# ip_phone_c_codec.net
KiCad netlist of a schematic drawn in Altium Designer
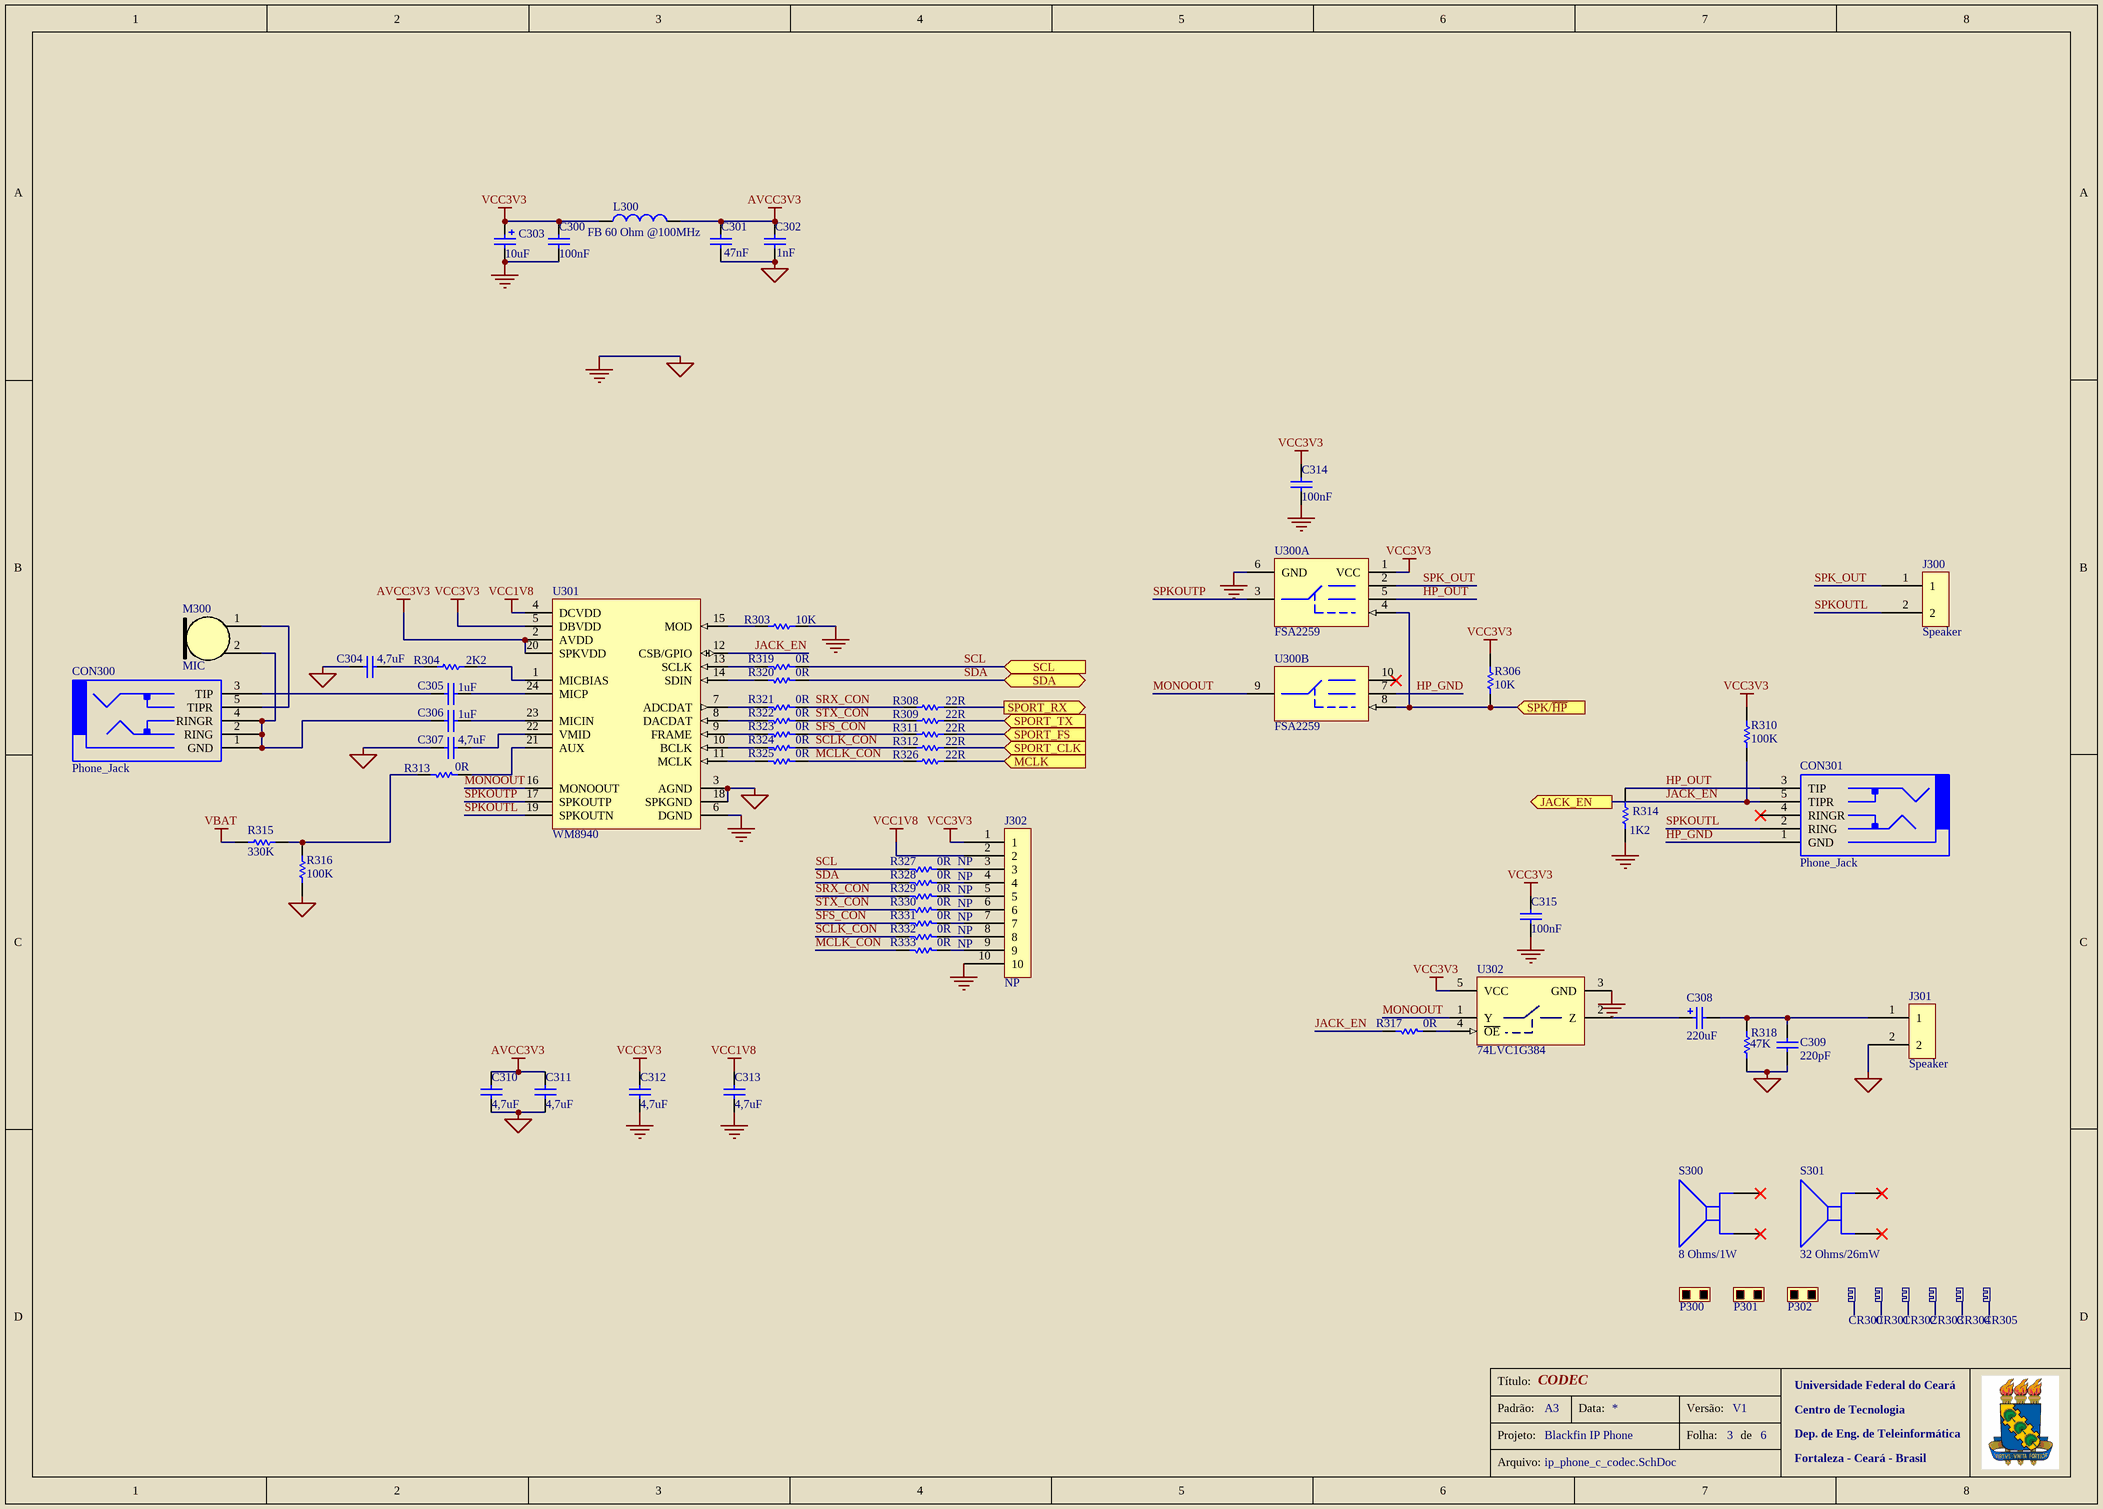
[diagram p0: ip_phone_c_codec.SchDoc]

(export (version "E")
  (design (tool "Eeschema 10.0.6"))
  (components
    (comp (ref "C300")
      (value "100nF")
      (footprint "ip_phone:CC1005-0402")
      (description "MLCC - SMD/SMT 100nF 16V 10% 0402")
      (fields (field (name "EVENDORPART#") "810-C1005X7R1C104K") (field (name "MANUFACTURER") "TDK"))
      (libsource (lib "ip_phone") (part "Capacitor"))
    )
    (comp (ref "C301")
      (value "47nF")
      (footprint "ip_phone:CC1005-0402")
      (description "MLCC - SMD/SMT 47nF 16V 10% 0402")
      (fields (field (name "EVENDORPART#") "311-1334-1-ND") (field (name "MANUFACTURER") "Yageo"))
      (libsource (lib "ip_phone") (part "Capacitor"))
    )
    (comp (ref "C302")
      (value "1nF")
      (footprint "ip_phone:CC1005-0402")
      (description "MLCC - SMD/SMT 1nF 16V 10% 0402")
      (fields (field (name "EVENDORPART#") "311-1352-1-ND") (field (name "MANUFACTURER") "Yageo"))
      (libsource (lib "ip_phone") (part "Capacitor"))
    )
    (comp (ref "C303")
      (value "10uF")
      (footprint "ip_phone:VE-100M0JTR-0305")
      (description "Aluminum Electrolytic Capacitors - SMD 6.3 Volts 10uF 20%")
      (fields (field (name "EVENDORPART#") "140-VE100M0JTR0305") (field (name "PART#") "VE-100M0JTR-0305"))
      (libsource (lib "ip_phone") (part "Capacitor_Electrolytic"))
    )
    (comp (ref "C304")
      (value "4,7uF")
      (footprint "ip_phone:CC1005-0402")
      (description "MLCC - SMD/SMT 4.7uF 20% 6.3Volts 0402")
      (fields (field (name "EVENDORPART#") "810-C1005X5R0J475M") (field (name "MANUFACTURER") "TDK"))
      (libsource (lib "ip_phone") (part "Capacitor"))
    )
    (comp (ref "C305")
      (value "1uF")
      (footprint "ip_phone:CC1005-0402")
      (description "CAP CER 1.0UF 6.3V 20% X5R 0402")
      (fields
        (field (name "EVENDORPART#") "490-1319-1-ND")
        (field (name "MANUFACTURER") "Murata Electronics North America")
      )
      (libsource (lib "ip_phone") (part "Capacitor"))
    )
    (comp (ref "C306")
      (value "1uF")
      (footprint "ip_phone:CC1005-0402")
      (description "CAP CER 1.0UF 6.3V 20% X5R 0402")
      (fields
        (field (name "EVENDORPART#") "490-1319-1-ND")
        (field (name "MANUFACTURER") "Murata Electronics North America")
      )
      (libsource (lib "ip_phone") (part "Capacitor"))
    )
    (comp (ref "C307")
      (value "4,7uF")
      (footprint "ip_phone:CC1005-0402")
      (description "MLCC - SMD/SMT 4.7uF 20% 6.3Volts 0402")
      (fields (field (name "EVENDORPART#") "810-C1005X5R0J475M") (field (name "MANUFACTURER") "TDK"))
      (libsource (lib "ip_phone") (part "Capacitor"))
    )
    (comp (ref "C308")
      (value "220uF")
      (footprint "ip_phone:CAP_VE221")
      (description "Aluminum Electrolytic Capacitors - SMD 6.3 Volts 220uF 20%")
      (fields (field (name "EVENDORPART#") "140-VE221M0JTR0605") (field (name "PART#") "VE-221M0JTR-0605"))
      (libsource (lib "ip_phone") (part "Capacitor_Electrolytic"))
    )
    (comp (ref "C309")
      (value "220pF")
      (footprint "ip_phone:CC1005-0402")
      (description "Capacitor 220pF 0402")
      (fields (field (name "EVENDORPART#") "311-1035-1-ND") (field (name "MANUFACTURER") "Yageo"))
      (libsource (lib "ip_phone") (part "Capacitor"))
    )
    (comp (ref "C310")
      (value "4,7uF")
      (footprint "ip_phone:CC1005-0402")
      (description "MLCC - SMD/SMT 4.7uF 20% 6.3Volts 0402")
      (fields (field (name "EVENDORPART#") "810-C1005X5R0J475M") (field (name "MANUFACTURER") "TDK"))
      (libsource (lib "ip_phone") (part "Capacitor"))
    )
    (comp (ref "C311")
      (value "4,7uF")
      (footprint "ip_phone:CC1005-0402")
      (description "MLCC - SMD/SMT 4.7uF 20% 6.3Volts 0402")
      (fields (field (name "EVENDORPART#") "810-C1005X5R0J475M") (field (name "MANUFACTURER") "TDK"))
      (libsource (lib "ip_phone") (part "Capacitor"))
    )
    (comp (ref "C312")
      (value "4,7uF")
      (footprint "ip_phone:CC1005-0402")
      (description "MLCC - SMD/SMT 4.7uF 20% 6.3Volts 0402")
      (fields (field (name "EVENDORPART#") "810-C1005X5R0J475M") (field (name "MANUFACTURER") "TDK"))
      (libsource (lib "ip_phone") (part "Capacitor"))
    )
    (comp (ref "C313")
      (value "4,7uF")
      (footprint "ip_phone:CC1005-0402")
      (description "MLCC - SMD/SMT 4.7uF 20% 6.3Volts 0402")
      (fields (field (name "EVENDORPART#") "810-C1005X5R0J475M") (field (name "MANUFACTURER") "TDK"))
      (libsource (lib "ip_phone") (part "Capacitor"))
    )
    (comp (ref "C314")
      (value "100nF")
      (footprint "ip_phone:CC1005-0402")
      (description "MLCC - SMD/SMT 0.1UF 16V 10% 0402")
      (fields (field (name "EVENDORPART#") "810-C1005X7R1C104K") (field (name "MANUFACTURER") "TDK"))
      (libsource (lib "ip_phone") (part "Capacitor"))
    )
    (comp (ref "C315")
      (value "100nF")
      (footprint "ip_phone:CC1005-0402")
      (description "MLCC - SMD/SMT 0.1UF 16V 10% 0402")
      (fields (field (name "EVENDORPART#") "810-C1005X7R1C104K") (field (name "MANUFACTURER") "TDK"))
      (libsource (lib "ip_phone") (part "Capacitor"))
    )
    (comp (ref "CON300")
      (value "Phone_Jack")
      (footprint "ip_phone:Phone_Jack")
      (fields
        (field (name "EVENDORPART#") "CP1-2535SJCT-ND")
        (field (name "MANUFACTURER") "CUI Inc")
        (field (name "PART#") "SJ1-2535-SMT")
      )
      (libsource (lib "") (part "Phone_Jack_1_1"))
    )
    (comp (ref "CON301")
      (value "Phone_Jack")
      (footprint "ip_phone:Phone_Jack")
      (fields
        (field (name "EVENDORPART#") "CP1-2535SJCT-ND")
        (field (name "MANUFACTURER") "CUI Inc")
        (field (name "PART#") "SJ1-2535-SMT")
      )
      (libsource (lib "ip_phone") (part "Phone_Jack_1"))
    )
    (comp (ref "CR300")
      (value "Crimp")
      (description "Socket Crimp")
      (fields (field (name "EVENDORPART#") "656-ILZC3A115000") (field (name "PART#") "IL-Z-C3-A-1-15000"))
      (libsource (lib "ip_phone") (part "Crimp"))
    )
    (comp (ref "CR301")
      (value "Crimp")
      (description "Socket Crimp")
      (fields (field (name "EVENDORPART#") "656-ILZC3A115000") (field (name "PART#") "IL-Z-C3-A-1-15000"))
      (libsource (lib "ip_phone") (part "Crimp"))
    )
    (comp (ref "CR302")
      (value "Crimp")
      (description "Socket Crimp")
      (fields (field (name "EVENDORPART#") "656-ILZC3A115000") (field (name "PART#") "IL-Z-C3-A-1-15000"))
      (libsource (lib "ip_phone") (part "Crimp"))
    )
    (comp (ref "CR303")
      (value "Crimp")
      (description "Socket Crimp")
      (fields (field (name "EVENDORPART#") "656-ILZC3A115000") (field (name "PART#") "IL-Z-C3-A-1-15000"))
      (libsource (lib "ip_phone") (part "Crimp"))
    )
    (comp (ref "CR304")
      (value "Crimp")
      (description "Socket Crimp")
      (fields (field (name "EVENDORPART#") "656-ILZC3A115000") (field (name "PART#") "IL-Z-C3-A-1-15000"))
      (libsource (lib "ip_phone") (part "Crimp"))
    )
    (comp (ref "CR305")
      (value "Crimp")
      (description "Socket Crimp")
      (fields (field (name "EVENDORPART#") "656-ILZC3A115000") (field (name "PART#") "IL-Z-C3-A-1-15000"))
      (libsource (lib "ip_phone") (part "Crimp"))
    )
    (comp (ref "J300")
      (value "Speaker")
      (footprint "ip_phone:CON_IL-Z-2PL")
      (description "Connector 2 Pin 1.25mm Male")
      (fields
        (field (name "EVENDORPART#") "656-IL-Z-2PL-SMTYE")
        (field (name "MANUFACTURER") "JAE Electronics")
      )
      (libsource (lib "ip_phone") (part "Speaker_con"))
    )
    (comp (ref "J301")
      (value "Speaker")
      (footprint "ip_phone:CON_IL-Z-2PL")
      (description "Connector 2 Pin 1.25mm Male")
      (fields
        (field (name "EVENDORPART#") "656-IL-Z-2PL-SMTYE")
        (field (name "MANUFACTURER") "JAE Electronics")
      )
      (libsource (lib "ip_phone") (part "Speaker_con"))
    )
    (comp (ref "J302")
      (value "CONN HEADER")
      (footprint "ip_phone:CONECTOR_10_PIN")
      (description "CONN HEADER .050\" 10POS PCB GOLD")
      (fields
        (field (name "EVENDORPART#") "S9014E-10-ND")
        (field (name "MANUFACTURER") "Sullins Connector Solutions")
        (field (name "NP") "NP")
      )
      (libsource (lib "ip_phone") (part "Conector 10pin"))
    )
    (comp (ref "L300")
      (value "FB 60 Ohm @100MHz")
      (footprint "ip_phone:INDUTOR_0603")
      (description "Ferrite Bead 60 Ohm @100MHz")
      (fields
        (field (name "EVENDORPART#") "667-EXC-3BP600H")
        (field (name "MANUFACTURER") "Panasonic Electronic Components")
      )
      (libsource (lib "ip_phone") (part "Inductor"))
    )
    (comp (ref "M300")
      (value "MIC")
      (footprint "ip_phone:CON_IL-Z-2PL")
      (description "Microphones -38DB 2VDC .5MA 2.2KOHM")
      (fields (field (name "PART#") "POM-2738P-C33-R") (field (name "MANUFACTURER") "PUI Audio"))
      (libsource (lib "ip_phone") (part "MIC"))
    )
    (comp (ref "P300")
      (value "Socket Housing")
      (description "Socket Housing 1.25mm 2 Pins")
      (fields (field (name "EVENDORPART#") "656-IL-Z-2S-S125C3") (field (name "PART#") "IL-Z-2S-S125C3"))
      (libsource (lib "ip_phone") (part "Socket Housing"))
    )
    (comp (ref "P301")
      (value "Socket Housing")
      (description "Socket Housing 1.25mm 2 Pins")
      (fields (field (name "EVENDORPART#") "656-IL-Z-2S-S125C3") (field (name "PART#") "IL-Z-2S-S125C3"))
      (libsource (lib "ip_phone") (part "Socket Housing"))
    )
    (comp (ref "P302")
      (value "Socket Housing")
      (description "Socket Housing 1.25mm 2 Pins")
      (fields (field (name "EVENDORPART#") "656-IL-Z-2S-S125C3") (field (name "PART#") "IL-Z-2S-S125C3"))
      (libsource (lib "ip_phone") (part "Socket Housing"))
    )
    (comp (ref "R303")
      (value "10K")
      (footprint "ip_phone:CR1005-0402")
      (description "Thick Film Resistors SMD 0402 10K 5%  1/16 W")
      (fields (field (name "EVENDORPART#") "311-10KJRCT-ND") (field (name "MANUFACTURER") "Yageo"))
      (libsource (lib "ip_phone") (part "Resistor"))
    )
    (comp (ref "R304")
      (value "2K2")
      (footprint "ip_phone:CR1005-0402")
      (description "Thick Film Resistors SMD 0402 2K2 5%  1/16 W")
      (fields (field (name "EVENDORPART#") "311-2.2KJRCT-ND") (field (name "MANUFACTURER") "Yageo"))
      (libsource (lib "ip_phone") (part "Resistor"))
    )
    (comp (ref "R306")
      (value "10K")
      (footprint "ip_phone:CR1005-0402")
      (description "Thick Film Resistors SMD 0402 10K 5%  1/16 W")
      (fields (field (name "EVENDORPART#") "311-10KJRCT-ND") (field (name "MANUFACTURER") "Yageo"))
      (libsource (lib "ip_phone") (part "Resistor"))
    )
    (comp (ref "R308")
      (value "22R")
      (footprint "ip_phone:CR1005-0402")
      (description "Thick Film Resistors SMD 0402 22R 5%  1/16 W")
      (fields (field (name "EVENDORPART#") "71-CRCW0402J-22-E3") (field (name "MANUFACTURER") "Vishay/Dale"))
      (libsource (lib "ip_phone") (part "Resistor"))
    )
    (comp (ref "R309")
      (value "22R")
      (footprint "ip_phone:CR1005-0402")
      (description "Thick Film Resistors SMD 0402 22R 5%  1/16 W")
      (fields (field (name "EVENDORPART#") "71-CRCW0402J-22-E3") (field (name "MANUFACTURER") "Vishay/Dale"))
      (libsource (lib "ip_phone") (part "Resistor"))
    )
    (comp (ref "R310")
      (value "100K")
      (footprint "ip_phone:CR1005-0402")
      (description "Thick Film Resistors SMD 0402 100K 5%  1/16 W")
      (fields (field (name "EVENDORPART#") "311-100KJRCT-ND") (field (name "MANUFACTURER") "Yageo"))
      (libsource (lib "ip_phone") (part "Resistor"))
    )
    (comp (ref "R311")
      (value "22R")
      (footprint "ip_phone:CR1005-0402")
      (description "Thick Film Resistors SMD 0402 22R 5%  1/16 W")
      (fields (field (name "EVENDORPART#") "71-CRCW0402J-22-E3") (field (name "MANUFACTURER") "Vishay/Dale"))
      (libsource (lib "ip_phone") (part "Resistor"))
    )
    (comp (ref "R312")
      (value "22R")
      (footprint "ip_phone:CR1005-0402")
      (description "Thick Film Resistors SMD 0402 22R 5%  1/16 W")
      (fields (field (name "EVENDORPART#") "71-CRCW0402J-22-E3") (field (name "MANUFACTURER") "Vishay/Dale"))
      (libsource (lib "ip_phone") (part "Resistor"))
    )
    (comp (ref "R313")
      (value "0R")
      (footprint "ip_phone:CR1005-0402")
      (description "Thick Film Resistors 0402 1/16W Jumper")
      (fields
        (field (name "EVENDORPART#") "667-ERJ-2GE0R00X")
        (field (name "MANUFACTURER") "Panasonic Electronic Components")
      )
      (libsource (lib "ip_phone") (part "Resistor"))
    )
    (comp (ref "R314")
      (value "1K2")
      (footprint "ip_phone:CR1005-0402")
      (description "Thick Film Resistors SMD 0402 1K2 5%  1/16 W")
      (fields (field (name "EVENDORPART#") "311-1.2KJRCT-ND") (field (name "MANUFACTURER") "Yageo"))
      (libsource (lib "ip_phone") (part "Resistor"))
    )
    (comp (ref "R315")
      (value "330K")
      (footprint "ip_phone:CR1005-0402")
      (description "Thick Film Resistor 330K 1% 1/16W")
      (fields
        (field (name "EVENDORPART#") "RMCF0402FT330KCT-ND")
        (field (name "MANUFACTURER") "Stackpole Electronics Inc")
      )
      (libsource (lib "ip_phone") (part "Resistor"))
    )
    (comp (ref "R316")
      (value "100K")
      (footprint "ip_phone:CR1005-0402")
      (description "Thick Film Resistors SMD 0402 100K 5%  1/16 W")
      (fields (field (name "EVENDORPART#") "311-100KJRCT-ND") (field (name "MANUFACTURER") "Yageo"))
      (libsource (lib "ip_phone") (part "Resistor"))
    )
    (comp (ref "R317")
      (value "0R")
      (footprint "ip_phone:CR1005-0402")
      (description "Thick Film Resistors 0402 1/16W Jumper")
      (fields
        (field (name "EVENDORPART#") "667-ERJ-2GE0R00X")
        (field (name "MANUFACTURER") "Panasonic Electronic Components")
      )
      (libsource (lib "ip_phone") (part "Resistor"))
    )
    (comp (ref "R318")
      (value "47K")
      (footprint "ip_phone:CR1005-0402")
      (description "Thick Film Resistors SMD 0402 47K 5%  1/16 W")
      (fields (field (name "EVENDORPART#") "311-47KJRCT-ND") (field (name "MANUFACTURER") "Yageo"))
      (libsource (lib "ip_phone") (part "Resistor"))
    )
    (comp (ref "R319")
      (value "0R")
      (footprint "ip_phone:CR1005-0402")
      (description "Thick Film Resistors 0402 1/16W Jumper")
      (fields
        (field (name "EVENDORPART#") "667-ERJ-2GE0R00X")
        (field (name "MANUFACTURER") "Panasonic Electronic Components")
      )
      (libsource (lib "ip_phone") (part "Resistor"))
    )
    (comp (ref "R320")
      (value "0R")
      (footprint "ip_phone:CR1005-0402")
      (description "Thick Film Resistors 0402 1/16W Jumper")
      (fields
        (field (name "EVENDORPART#") "667-ERJ-2GE0R00X")
        (field (name "MANUFACTURER") "Panasonic Electronic Components")
      )
      (libsource (lib "ip_phone") (part "Resistor"))
    )
    (comp (ref "R321")
      (value "0R")
      (footprint "ip_phone:CR1005-0402")
      (description "Thick Film Resistors 0402 1/16W Jumper")
      (fields
        (field (name "EVENDORPART#") "667-ERJ-2GE0R00X")
        (field (name "MANUFACTURER") "Panasonic Electronic Components")
      )
      (libsource (lib "ip_phone") (part "Resistor"))
    )
    (comp (ref "R322")
      (value "0R")
      (footprint "ip_phone:CR1005-0402")
      (description "Thick Film Resistors 0402 1/16W Jumper")
      (fields
        (field (name "EVENDORPART#") "667-ERJ-2GE0R00X")
        (field (name "MANUFACTURER") "Panasonic Electronic Components")
      )
      (libsource (lib "ip_phone") (part "Resistor"))
    )
    (comp (ref "R323")
      (value "0R")
      (footprint "ip_phone:CR1005-0402")
      (description "Thick Film Resistors 0402 1/16W Jumper")
      (fields
        (field (name "EVENDORPART#") "667-ERJ-2GE0R00X")
        (field (name "MANUFACTURER") "Panasonic Electronic Components")
      )
      (libsource (lib "ip_phone") (part "Resistor"))
    )
    (comp (ref "R324")
      (value "0R")
      (footprint "ip_phone:CR1005-0402")
      (description "Thick Film Resistors 0402 1/16W Jumper")
      (fields
        (field (name "EVENDORPART#") "667-ERJ-2GE0R00X")
        (field (name "MANUFACTURER") "Panasonic Electronic Components")
      )
      (libsource (lib "ip_phone") (part "Resistor"))
    )
    (comp (ref "R325")
      (value "0R")
      (footprint "ip_phone:CR1005-0402")
      (description "Thick Film Resistors 0402 1/16W Jumper")
      (fields
        (field (name "EVENDORPART#") "667-ERJ-2GE0R00X")
        (field (name "MANUFACTURER") "Panasonic Electronic Components")
      )
      (libsource (lib "ip_phone") (part "Resistor"))
    )
    (comp (ref "R326")
      (value "22R")
      (footprint "ip_phone:CR1005-0402")
      (description "Thick Film Resistors SMD 0402 22R 5%  1/16 W")
      (fields (field (name "EVENDORPART#") "71-CRCW0402J-22-E3") (field (name "MANUFACTURER") "Vishay/Dale"))
      (libsource (lib "ip_phone") (part "Resistor"))
    )
    (comp (ref "R327")
      (value "0R")
      (footprint "ip_phone:CR1005-0402")
      (description "Thick Film Resistors 0402 1/16W Jumper")
      (fields
        (field (name "EVENDORPART#") "667-ERJ-2GE0R00X")
        (field (name "MANUFACTURER") "Panasonic Electronic Components")
        (field (name "NP") "NP")
      )
      (libsource (lib "ip_phone") (part "Resistor"))
    )
    (comp (ref "R328")
      (value "0R")
      (footprint "ip_phone:CR1005-0402")
      (description "Thick Film Resistors 0402 1/16W Jumper")
      (fields
        (field (name "EVENDORPART#") "667-ERJ-2GE0R00X")
        (field (name "MANUFACTURER") "Panasonic Electronic Components")
        (field (name "NP") "NP")
      )
      (libsource (lib "ip_phone") (part "Resistor"))
    )
    (comp (ref "R329")
      (value "0R")
      (footprint "ip_phone:CR1005-0402")
      (description "Thick Film Resistors 0402 1/16W Jumper")
      (fields
        (field (name "EVENDORPART#") "667-ERJ-2GE0R00X")
        (field (name "MANUFACTURER") "Panasonic Electronic Components")
        (field (name "NP") "NP")
      )
      (libsource (lib "ip_phone") (part "Resistor"))
    )
    (comp (ref "R330")
      (value "0R")
      (footprint "ip_phone:CR1005-0402")
      (description "Thick Film Resistors 0402 1/16W Jumper")
      (fields
        (field (name "EVENDORPART#") "667-ERJ-2GE0R00X")
        (field (name "MANUFACTURER") "Panasonic Electronic Components")
        (field (name "NP") "NP")
      )
      (libsource (lib "ip_phone") (part "Resistor"))
    )
    (comp (ref "R331")
      (value "0R")
      (footprint "ip_phone:CR1005-0402")
      (description "Thick Film Resistors 0402 1/16W Jumper")
      (fields
        (field (name "EVENDORPART#") "667-ERJ-2GE0R00X")
        (field (name "MANUFACTURER") "Panasonic Electronic Components")
        (field (name "NP") "NP")
      )
      (libsource (lib "ip_phone") (part "Resistor"))
    )
    (comp (ref "R332")
      (value "0R")
      (footprint "ip_phone:CR1005-0402")
      (description "Thick Film Resistors 0402 1/16W Jumper")
      (fields
        (field (name "EVENDORPART#") "667-ERJ-2GE0R00X")
        (field (name "MANUFACTURER") "Panasonic Electronic Components")
        (field (name "NP") "NP")
      )
      (libsource (lib "ip_phone") (part "Resistor"))
    )
    (comp (ref "R333")
      (value "0R")
      (footprint "ip_phone:CR1005-0402")
      (description "Thick Film Resistors 0402 1/16W Jumper")
      (fields
        (field (name "EVENDORPART#") "667-ERJ-2GE0R00X")
        (field (name "MANUFACTURER") "Panasonic Electronic Components")
        (field (name "NP") "NP")
      )
      (libsource (lib "ip_phone") (part "Resistor"))
    )
    (comp (ref "S300")
      (value "8 Ohms/1W")
      (description "Speaker 8 Ohms 1W")
      (fields (field (name "EVENDORPART#") "254-DS238-RO") (field (name "MANUFACTURER") "Kobitone"))
      (libsource (lib "ip_phone") (part "Speaker"))
    )
    (comp (ref "S301")
      (value "32 Ohms/26mW")
      (description "Dynamic Receiver 32Ohms 26mW 115dB 13mm D")
      (fields (field (name "EVENDORPART#") "254-DR132-RO") (field (name "MANUFACTURER") "Kobitone"))
      (libsource (lib "ip_phone") (part "Receiver"))
    )
    (comp (ref "U300")
      (value "FSA2259")
      (footprint "ip_phone:QFN-10FSA")
      (description "Analog Switch, Dual SPDT")
      (fields
        (field (name "EVENDORPART#") "512-FSA2259UMX")
        (field (name "MANUFACTURER") "Fairchild Semiconductor")
      )
      (libsource (lib "ip_phone") (part "FSA2259"))
    )
    (comp (ref "U301")
      (value "WM8940")
      (footprint "ip_phone:QFN24")
      (description "Mono Audio CODEC")
      (fields (field (name "EVENDORPART#") "238-WM8940GEFL/V") (field (name "PART#") "WM8940GEFL/V"))
      (libsource (lib "ip_phone") (part "WM8940"))
    )
    (comp (ref "U302")
      (value "74LVC1G384")
      (footprint "ip_phone:SOT753")
      (description "Low Voltage SPST Analog Switch")
      (fields (field (name "EVENDORPART#") "771-LVC1G384GV125") (field (name "PART#") "74LVC1G384GV,125"))
      (libsource (lib "ip_phone") (part "74LVC1G384"))
    )
  )
  (nets
    (net (code "1") (name "/HP_GND") (class "Default")
      (node (ref "CON301") (pin "1") (pinfunction "GND_1") (pintype "passive"))
      (node (ref "U300") (pin "7") (pinfunction "2B0_7") (pintype "passive"))
    )
    (net (code "2") (name "/HP_OUT") (class "Default")
      (node (ref "CON301") (pin "3") (pinfunction "TIP_3") (pintype "passive"))
      (node (ref "R314") (pin "1") (pinfunction "1_1") (pintype "passive"))
      (node (ref "U300") (pin "5") (pinfunction "1B0_5") (pintype "passive"))
    )
    (net (code "3") (name "/JACK_EN") (class "Default")
      (node (ref "CON301") (pin "5") (pinfunction "TIPR_5") (pintype "passive"))
      (node (ref "R310") (pin "1") (pinfunction "1_1") (pintype "passive"))
      (node (ref "R317") (pin "2") (pinfunction "2_2") (pintype "passive"))
      (node (ref "U301") (pin "12") (pinfunction "CSB/GPIO_12") (pintype "bidirectional"))
    )
    (net (code "4") (name "/MCLK") (class "Default")
      (node (ref "R326") (pin "2") (pinfunction "2_2") (pintype "passive"))
    )
    (net (code "5") (name "/MCLK_CON") (class "Default")
      (node (ref "R325") (pin "1") (pinfunction "1_1") (pintype "passive"))
      (node (ref "R326") (pin "1") (pinfunction "1_1") (pintype "passive"))
      (node (ref "R333") (pin "2") (pinfunction "2_2") (pintype "passive"))
    )
    (net (code "6") (name "/MONOOUT") (class "Default")
      (node (ref "U300") (pin "9") (pinfunction "2A_9") (pintype "passive"))
      (node (ref "U301") (pin "16") (pinfunction "MONOOUT_16") (pintype "passive"))
      (node (ref "U302") (pin "1") (pinfunction "Y_1") (pintype "passive"))
    )
    (net (code "7") (name "/SCL") (class "Default")
      (node (ref "R319") (pin "1") (pinfunction "1_1") (pintype "passive"))
      (node (ref "R327") (pin "2") (pinfunction "2_2") (pintype "passive"))
    )
    (net (code "8") (name "/SCLK_CON") (class "Default")
      (node (ref "R312") (pin "1") (pinfunction "1_1") (pintype "passive"))
      (node (ref "R324") (pin "1") (pinfunction "1_1") (pintype "passive"))
      (node (ref "R332") (pin "2") (pinfunction "2_2") (pintype "passive"))
    )
    (net (code "9") (name "/SDA") (class "Default")
      (node (ref "R320") (pin "1") (pinfunction "1_1") (pintype "passive"))
      (node (ref "R328") (pin "2") (pinfunction "2_2") (pintype "passive"))
    )
    (net (code "10") (name "/SFS_CON") (class "Default")
      (node (ref "R311") (pin "1") (pinfunction "1_1") (pintype "passive"))
      (node (ref "R323") (pin "1") (pinfunction "1_1") (pintype "passive"))
      (node (ref "R331") (pin "2") (pinfunction "2_2") (pintype "passive"))
    )
    (net (code "11") (name "/SPKOUTL") (class "Default")
      (node (ref "CON301") (pin "2") (pinfunction "RING_2") (pintype "passive"))
      (node (ref "J300") (pin "2") (pinfunction "2_2") (pintype "passive"))
      (node (ref "U301") (pin "19") (pinfunction "SPKOUTN_19") (pintype "passive"))
    )
    (net (code "12") (name "/SPKOUTP") (class "Default")
      (node (ref "U300") (pin "3") (pinfunction "1A_3") (pintype "passive"))
      (node (ref "U301") (pin "17") (pinfunction "SPKOUTP_17") (pintype "passive"))
    )
    (net (code "13") (name "/SPK_OUT") (class "Default")
      (node (ref "J300") (pin "1") (pinfunction "1_1") (pintype "passive"))
      (node (ref "U300") (pin "2") (pinfunction "1B1_2") (pintype "passive"))
    )
    (net (code "14") (name "/SPK{slash}~{HP}") (class "Default")
      (node (ref "R306") (pin "1") (pinfunction "1_1") (pintype "passive"))
      (node (ref "U300") (pin "4") (pinfunction "S1_4") (pintype "input"))
      (node (ref "U300") (pin "8") (pinfunction "S2_8") (pintype "input"))
    )
    (net (code "15") (name "/SPORT_CLK") (class "Default")
      (node (ref "R312") (pin "2") (pinfunction "2_2") (pintype "passive"))
    )
    (net (code "16") (name "/SPORT_FS") (class "Default")
      (node (ref "R311") (pin "2") (pinfunction "2_2") (pintype "passive"))
    )
    (net (code "17") (name "/SPORT_RX") (class "Default")
      (node (ref "R308") (pin "2") (pinfunction "2_2") (pintype "passive"))
    )
    (net (code "18") (name "/SPORT_TX") (class "Default")
      (node (ref "R309") (pin "2") (pinfunction "2_2") (pintype "passive"))
    )
    (net (code "19") (name "/SRX_CON") (class "Default")
      (node (ref "R308") (pin "1") (pinfunction "1_1") (pintype "passive"))
      (node (ref "R321") (pin "1") (pinfunction "1_1") (pintype "passive"))
      (node (ref "R329") (pin "2") (pinfunction "2_2") (pintype "passive"))
    )
    (net (code "20") (name "/STX_CON") (class "Default")
      (node (ref "R309") (pin "1") (pinfunction "1_1") (pintype "passive"))
      (node (ref "R322") (pin "1") (pinfunction "1_1") (pintype "passive"))
      (node (ref "R330") (pin "2") (pinfunction "2_2") (pintype "passive"))
    )
    (net (code "21") (name "AGND") (class "Default")
      (node (ref "C300") (pin "1") (pinfunction "1_1") (pintype "passive"))
      (node (ref "C301") (pin "1") (pinfunction "1_1") (pintype "passive"))
      (node (ref "C302") (pin "1") (pinfunction "1_1") (pintype "passive"))
      (node (ref "C303") (pin "2") (pinfunction "2_2") (pintype "passive"))
      (node (ref "C304") (pin "1") (pinfunction "1_1") (pintype "passive"))
      (node (ref "C307") (pin "1") (pinfunction "1_1") (pintype "passive"))
      (node (ref "C309") (pin "1") (pinfunction "1_1") (pintype "passive"))
      (node (ref "C310") (pin "2") (pinfunction "2_2") (pintype "passive"))
      (node (ref "C311") (pin "2") (pinfunction "2_2") (pintype "passive"))
      (node (ref "C312") (pin "2") (pinfunction "2_2") (pintype "passive"))
      (node (ref "C313") (pin "2") (pinfunction "2_2") (pintype "passive"))
      (node (ref "C314") (pin "1") (pinfunction "1_1") (pintype "passive"))
      (node (ref "C315") (pin "1") (pinfunction "1_1") (pintype "passive"))
      (node (ref "J301") (pin "2") (pinfunction "2_2") (pintype "passive"))
      (node (ref "J302") (pin "10") (pinfunction "10_10") (pintype "passive"))
      (node (ref "R303") (pin "2") (pinfunction "2_2") (pintype "passive"))
      (node (ref "R314") (pin "2") (pinfunction "2_2") (pintype "passive"))
      (node (ref "R316") (pin "1") (pinfunction "1_1") (pintype "passive"))
      (node (ref "R318") (pin "2") (pinfunction "2_2") (pintype "passive"))
      (node (ref "U300") (pin "6") (pinfunction "GND_6") (pintype "power_in"))
      (node (ref "U301") (pin "18") (pinfunction "SPKGND_18") (pintype "passive"))
      (node (ref "U301") (pin "3") (pinfunction "AGND_3") (pintype "power_in"))
      (node (ref "U301") (pin "6") (pinfunction "DGND_6") (pintype "power_in"))
      (node (ref "U302") (pin "3") (pinfunction "GND_3") (pintype "power_in"))
    )
    (net (code "22") (name "AVCC3V3") (class "Default")
      (node (ref "C301") (pin "2") (pinfunction "2_2") (pintype "passive"))
      (node (ref "C302") (pin "2") (pinfunction "2_2") (pintype "passive"))
      (node (ref "C310") (pin "1") (pinfunction "1_1") (pintype "passive"))
      (node (ref "C311") (pin "1") (pinfunction "1_1") (pintype "passive"))
      (node (ref "L300") (pin "2") (pinfunction "2_2") (pintype "passive"))
      (node (ref "U301") (pin "2") (pinfunction "AVDD_2") (pintype "power_in"))
      (node (ref "U301") (pin "20") (pinfunction "SPKVDD_20") (pintype "power_in"))
    )
    (net (code "23") (name "Net-(C304-Pad2)") (class "Default")
      (node (ref "C304") (pin "2") (pinfunction "2_2") (pintype "passive"))
      (node (ref "R304") (pin "1") (pinfunction "1_1") (pintype "passive"))
    )
    (net (code "24") (name "Net-(C308-Pad2)") (class "Default")
      (node (ref "C308") (pin "2") (pinfunction "2_2") (pintype "passive"))
      (node (ref "C309") (pin "2") (pinfunction "2_2") (pintype "passive"))
      (node (ref "J301") (pin "1") (pinfunction "1_1") (pintype "passive"))
      (node (ref "R318") (pin "1") (pinfunction "1_1") (pintype "passive"))
    )
    (net (code "25") (name "Net-(CON300-GND)") (class "Default")
      (node (ref "C306") (pin "2") (pinfunction "2_2") (pintype "passive"))
      (node (ref "CON300") (pin "1") (pinfunction "GND_1") (pintype "passive"))
      (node (ref "CON300") (pin "2") (pinfunction "RING_2") (pintype "passive"))
      (node (ref "CON300") (pin "4") (pinfunction "RINGR_4") (pintype "passive"))
      (node (ref "M300") (pin "2") (pinfunction "GND_2") (pintype "power_in"))
    )
    (net (code "26") (name "Net-(CON300-TIP)") (class "Default")
      (node (ref "C305") (pin "2") (pinfunction "2_2") (pintype "passive"))
      (node (ref "CON300") (pin "3") (pinfunction "TIP_3") (pintype "passive"))
    )
    (net (code "27") (name "Net-(CON300-TIPR)") (class "Default")
      (node (ref "CON300") (pin "5") (pinfunction "TIPR_5") (pintype "passive"))
      (node (ref "M300") (pin "1") (pinfunction "OUT_1") (pintype "passive"))
    )
    (net (code "28") (name "Net-(J302-Pad3)") (class "Default")
      (node (ref "J302") (pin "3") (pinfunction "3_3") (pintype "passive"))
      (node (ref "R327") (pin "1") (pinfunction "1_1") (pintype "passive"))
    )
    (net (code "29") (name "Net-(J302-Pad4)") (class "Default")
      (node (ref "J302") (pin "4") (pinfunction "4_4") (pintype "passive"))
      (node (ref "R328") (pin "1") (pinfunction "1_1") (pintype "passive"))
    )
    (net (code "30") (name "Net-(J302-Pad5)") (class "Default")
      (node (ref "J302") (pin "5") (pinfunction "5_5") (pintype "passive"))
      (node (ref "R329") (pin "1") (pinfunction "1_1") (pintype "passive"))
    )
    (net (code "31") (name "Net-(J302-Pad6)") (class "Default")
      (node (ref "J302") (pin "6") (pinfunction "6_6") (pintype "passive"))
      (node (ref "R330") (pin "1") (pinfunction "1_1") (pintype "passive"))
    )
    (net (code "32") (name "Net-(J302-Pad7)") (class "Default")
      (node (ref "J302") (pin "7") (pinfunction "7_7") (pintype "passive"))
      (node (ref "R331") (pin "1") (pinfunction "1_1") (pintype "passive"))
    )
    (net (code "33") (name "Net-(J302-Pad8)") (class "Default")
      (node (ref "J302") (pin "8") (pinfunction "8_8") (pintype "passive"))
      (node (ref "R332") (pin "1") (pinfunction "1_1") (pintype "passive"))
    )
    (net (code "34") (name "Net-(J302-Pad9)") (class "Default")
      (node (ref "J302") (pin "9") (pinfunction "9_9") (pintype "passive"))
      (node (ref "R333") (pin "1") (pinfunction "1_1") (pintype "passive"))
    )
    (net (code "35") (name "Net-(R313-Pad2)") (class "Default")
      (node (ref "R313") (pin "2") (pinfunction "2_2") (pintype "passive"))
      (node (ref "R315") (pin "2") (pinfunction "2_2") (pintype "passive"))
      (node (ref "R316") (pin "2") (pinfunction "2_2") (pintype "passive"))
    )
    (net (code "36") (name "Net-(U301-ADCDAT)") (class "Default")
      (node (ref "R321") (pin "2") (pinfunction "2_2") (pintype "passive"))
      (node (ref "U301") (pin "7") (pinfunction "ADCDAT_7") (pintype "output"))
    )
    (net (code "37") (name "Net-(U301-AUX)") (class "Default")
      (node (ref "R313") (pin "1") (pinfunction "1_1") (pintype "passive"))
      (node (ref "U301") (pin "21") (pinfunction "AUX_21") (pintype "passive"))
    )
    (net (code "38") (name "Net-(U301-BCLK)") (class "Default")
      (node (ref "R324") (pin "2") (pinfunction "2_2") (pintype "passive"))
      (node (ref "U301") (pin "10") (pinfunction "BCLK_10") (pintype "input"))
    )
    (net (code "39") (name "Net-(U301-DACDAT)") (class "Default")
      (node (ref "R322") (pin "2") (pinfunction "2_2") (pintype "passive"))
      (node (ref "U301") (pin "8") (pinfunction "DACDAT_8") (pintype "input"))
    )
    (net (code "40") (name "Net-(U301-FRAME)") (class "Default")
      (node (ref "R323") (pin "2") (pinfunction "2_2") (pintype "passive"))
      (node (ref "U301") (pin "9") (pinfunction "FRAME_9") (pintype "input"))
    )
    (net (code "41") (name "Net-(U301-MCLK)") (class "Default")
      (node (ref "R325") (pin "2") (pinfunction "2_2") (pintype "passive"))
      (node (ref "U301") (pin "11") (pinfunction "MCLK_11") (pintype "input"))
    )
    (net (code "42") (name "Net-(U301-MICBIAS)") (class "Default")
      (node (ref "R304") (pin "2") (pinfunction "2_2") (pintype "passive"))
      (node (ref "U301") (pin "1") (pinfunction "MICBIAS_1") (pintype "passive"))
    )
    (net (code "43") (name "Net-(U301-MICIN)") (class "Default")
      (node (ref "C306") (pin "1") (pinfunction "1_1") (pintype "passive"))
      (node (ref "U301") (pin "23") (pinfunction "MICIN_23") (pintype "passive"))
    )
    (net (code "44") (name "Net-(U301-MICP)") (class "Default")
      (node (ref "C305") (pin "1") (pinfunction "1_1") (pintype "passive"))
      (node (ref "U301") (pin "24") (pinfunction "MICP_24") (pintype "passive"))
    )
    (net (code "45") (name "Net-(U301-MOD)") (class "Default")
      (node (ref "R303") (pin "1") (pinfunction "1_1") (pintype "passive"))
      (node (ref "U301") (pin "15") (pinfunction "MOD_15") (pintype "input"))
    )
    (net (code "46") (name "Net-(U301-SCLK)") (class "Default")
      (node (ref "R319") (pin "2") (pinfunction "2_2") (pintype "passive"))
      (node (ref "U301") (pin "13") (pinfunction "SCLK_13") (pintype "input"))
    )
    (net (code "47") (name "Net-(U301-SDIN)") (class "Default")
      (node (ref "R320") (pin "2") (pinfunction "2_2") (pintype "passive"))
      (node (ref "U301") (pin "14") (pinfunction "SDIN_14") (pintype "input"))
    )
    (net (code "48") (name "Net-(U301-VMID)") (class "Default")
      (node (ref "C307") (pin "2") (pinfunction "2_2") (pintype "passive"))
      (node (ref "U301") (pin "22") (pinfunction "VMID_22") (pintype "passive"))
    )
    (net (code "49") (name "Net-(U302-OE)") (class "Default")
      (node (ref "R317") (pin "1") (pinfunction "1_1") (pintype "passive"))
      (node (ref "U302") (pin "4") (pinfunction "OE_4") (pintype "input"))
    )
    (net (code "50") (name "Net-(U302-Z)") (class "Default")
      (node (ref "C308") (pin "1") (pinfunction "1_1") (pintype "passive"))
      (node (ref "U302") (pin "2") (pinfunction "Z_2") (pintype "passive"))
    )
    (net (code "51") (name "VBAT") (class "Default")
      (node (ref "R315") (pin "1") (pinfunction "1_1") (pintype "passive"))
    )
    (net (code "52") (name "VCC1V8") (class "Default")
      (node (ref "C313") (pin "1") (pinfunction "1_1") (pintype "passive"))
      (node (ref "J302") (pin "2") (pinfunction "2_2") (pintype "passive"))
      (node (ref "U301") (pin "4") (pinfunction "DCVDD_4") (pintype "power_in"))
    )
    (net (code "53") (name "VCC3V3") (class "Default")
      (node (ref "C300") (pin "2") (pinfunction "2_2") (pintype "passive"))
      (node (ref "C303") (pin "1") (pinfunction "1_1") (pintype "passive"))
      (node (ref "C312") (pin "1") (pinfunction "1_1") (pintype "passive"))
      (node (ref "C314") (pin "2") (pinfunction "2_2") (pintype "passive"))
      (node (ref "C315") (pin "2") (pinfunction "2_2") (pintype "passive"))
      (node (ref "J302") (pin "1") (pinfunction "1_1") (pintype "passive"))
      (node (ref "L300") (pin "1") (pinfunction "1_1") (pintype "passive"))
      (node (ref "R306") (pin "2") (pinfunction "2_2") (pintype "passive"))
      (node (ref "R310") (pin "2") (pinfunction "2_2") (pintype "passive"))
      (node (ref "U300") (pin "1") (pinfunction "VCC_1") (pintype "passive"))
      (node (ref "U301") (pin "5") (pinfunction "DBVDD_5") (pintype "power_in"))
      (node (ref "U302") (pin "5") (pinfunction "VCC_5") (pintype "power_in"))
    )
    (net (code "54") (name "unconnected-(CON301-RINGR-Pad4)") (class "Default")
      (node (ref "CON301") (pin "4") (pinfunction "RINGR_4") (pintype "passive+no_connect"))
    )
    (net (code "55") (name "unconnected-(S300-CKT1-Pad1)") (class "Default")
      (node (ref "S300") (pin "1") (pinfunction "CKT1_1") (pintype "passive+no_connect"))
    )
    (net (code "56") (name "unconnected-(S300-CKT2-Pad2)") (class "Default")
      (node (ref "S300") (pin "2") (pinfunction "CKT2_2") (pintype "passive+no_connect"))
    )
    (net (code "57") (name "unconnected-(S301-CKT1-Pad1)") (class "Default")
      (node (ref "S301") (pin "1") (pinfunction "CKT1_1") (pintype "passive+no_connect"))
    )
    (net (code "58") (name "unconnected-(S301-CKT2-Pad2)") (class "Default")
      (node (ref "S301") (pin "2") (pinfunction "CKT2_2") (pintype "passive+no_connect"))
    )
    (net (code "59") (name "unconnected-(U300B-2B1-Pad10)") (class "Default")
      (node (ref "U300") (pin "10") (pinfunction "2B1_10") (pintype "passive+no_connect"))
    )
  )
)
